# 5vAC-DCCReg.net
KiCad netlist of a schematic drawn in EAGLE
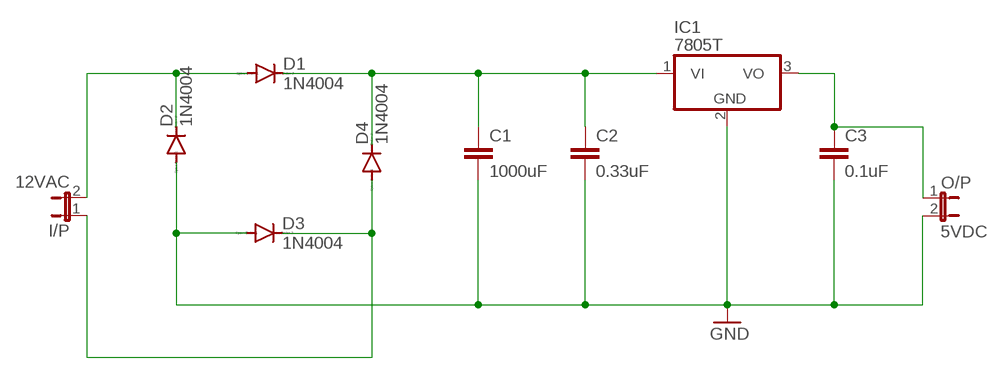
[diagram p0: schematic, sheet 1]

(export (version "E")
  (design (tool "Eeschema 10.0.6"))
  (components
    (comp (ref "C1")
      (value "1000uF")
      (footprint "eagle-import:C2.5-3")
      (libsource (lib "eagle-import") (part "C2,5-3"))
    )
    (comp (ref "C2")
      (value "0.33uF")
      (footprint "eagle-import:C2.5-3")
      (libsource (lib "eagle-import") (part "C2,5-3"))
    )
    (comp (ref "C3")
      (value "0.1uF")
      (footprint "eagle-import:C2.5-3")
      (libsource (lib "eagle-import") (part "C2,5-3"))
    )
    (comp (ref "D1")
      (value "1N4004")
      (footprint "eagle-import:DO41-10")
      (libsource (lib "eagle-import") (part "1N4004"))
    )
    (comp (ref "D2")
      (value "1N4004")
      (footprint "eagle-import:DO41-10")
      (libsource (lib "eagle-import") (part "1N4004"))
    )
    (comp (ref "D3")
      (value "1N4004")
      (footprint "eagle-import:DO41-10")
      (libsource (lib "eagle-import") (part "1N4004"))
    )
    (comp (ref "D4")
      (value "1N4004")
      (footprint "eagle-import:DO41-10")
      (libsource (lib "eagle-import") (part "1N4004"))
    )
    (comp (ref "I/P")
      (value "12VAC")
      (footprint "eagle-import:JP1")
      (libsource (lib "eagle-import") (part "JP1E"))
    )
    (comp (ref "IC1")
      (value "7805T")
      (footprint "eagle-import:TO220H")
      (libsource (lib "eagle-import") (part "78T05"))
    )
    (comp (ref "O/P")
      (value "5VDC")
      (footprint "eagle-import:JP1")
      (libsource (lib "eagle-import") (part "JP1E"))
    )
  )
  (nets
    (net (code "1") (name "GND") (class "Default")
      (node (ref "C1") (pin "2") (pinfunction "2_2") (pintype "passive"))
      (node (ref "C2") (pin "2") (pinfunction "2_2") (pintype "passive"))
      (node (ref "C3") (pin "2") (pinfunction "2_2") (pintype "passive"))
      (node (ref "D2") (pin "A") (pinfunction "A_A") (pintype "passive"))
      (node (ref "D3") (pin "A") (pinfunction "A_A") (pintype "passive"))
      (node (ref "IC1") (pin "2") (pinfunction "GND_2") (pintype "passive"))
      (node (ref "O/P") (pin "2") (pinfunction "2_2") (pintype "passive"))
    )
    (net (code "2") (name "Net-(D1-PadA)") (class "Default")
      (node (ref "D1") (pin "A") (pinfunction "A_A") (pintype "passive"))
      (node (ref "D2") (pin "C") (pinfunction "C_C") (pintype "passive"))
      (node (ref "I/P") (pin "2") (pinfunction "2_2") (pintype "passive"))
    )
    (net (code "3") (name "Net-(D3-PadC)") (class "Default")
      (node (ref "D3") (pin "C") (pinfunction "C_C") (pintype "passive"))
      (node (ref "D4") (pin "A") (pinfunction "A_A") (pintype "passive"))
      (node (ref "I/P") (pin "1") (pinfunction "1_1") (pintype "passive"))
    )
    (net (code "4") (name "Net-(IC1-VI)") (class "Default")
      (node (ref "C1") (pin "1") (pinfunction "1_1") (pintype "passive"))
      (node (ref "C2") (pin "1") (pinfunction "1_1") (pintype "passive"))
      (node (ref "D1") (pin "C") (pinfunction "C_C") (pintype "passive"))
      (node (ref "D4") (pin "C") (pinfunction "C_C") (pintype "passive"))
      (node (ref "IC1") (pin "1") (pinfunction "VI_1") (pintype "input"))
    )
    (net (code "5") (name "Net-(IC1-VO)") (class "Default")
      (node (ref "C3") (pin "1") (pinfunction "1_1") (pintype "passive"))
      (node (ref "IC1") (pin "3") (pinfunction "VO_3") (pintype "passive"))
      (node (ref "O/P") (pin "1") (pinfunction "1_1") (pintype "passive"))
    )
  )
)
